# 105358-3SC001-01-A_BlockDiagram.net
KiCad netlist of a schematic drawn in Altium Designer
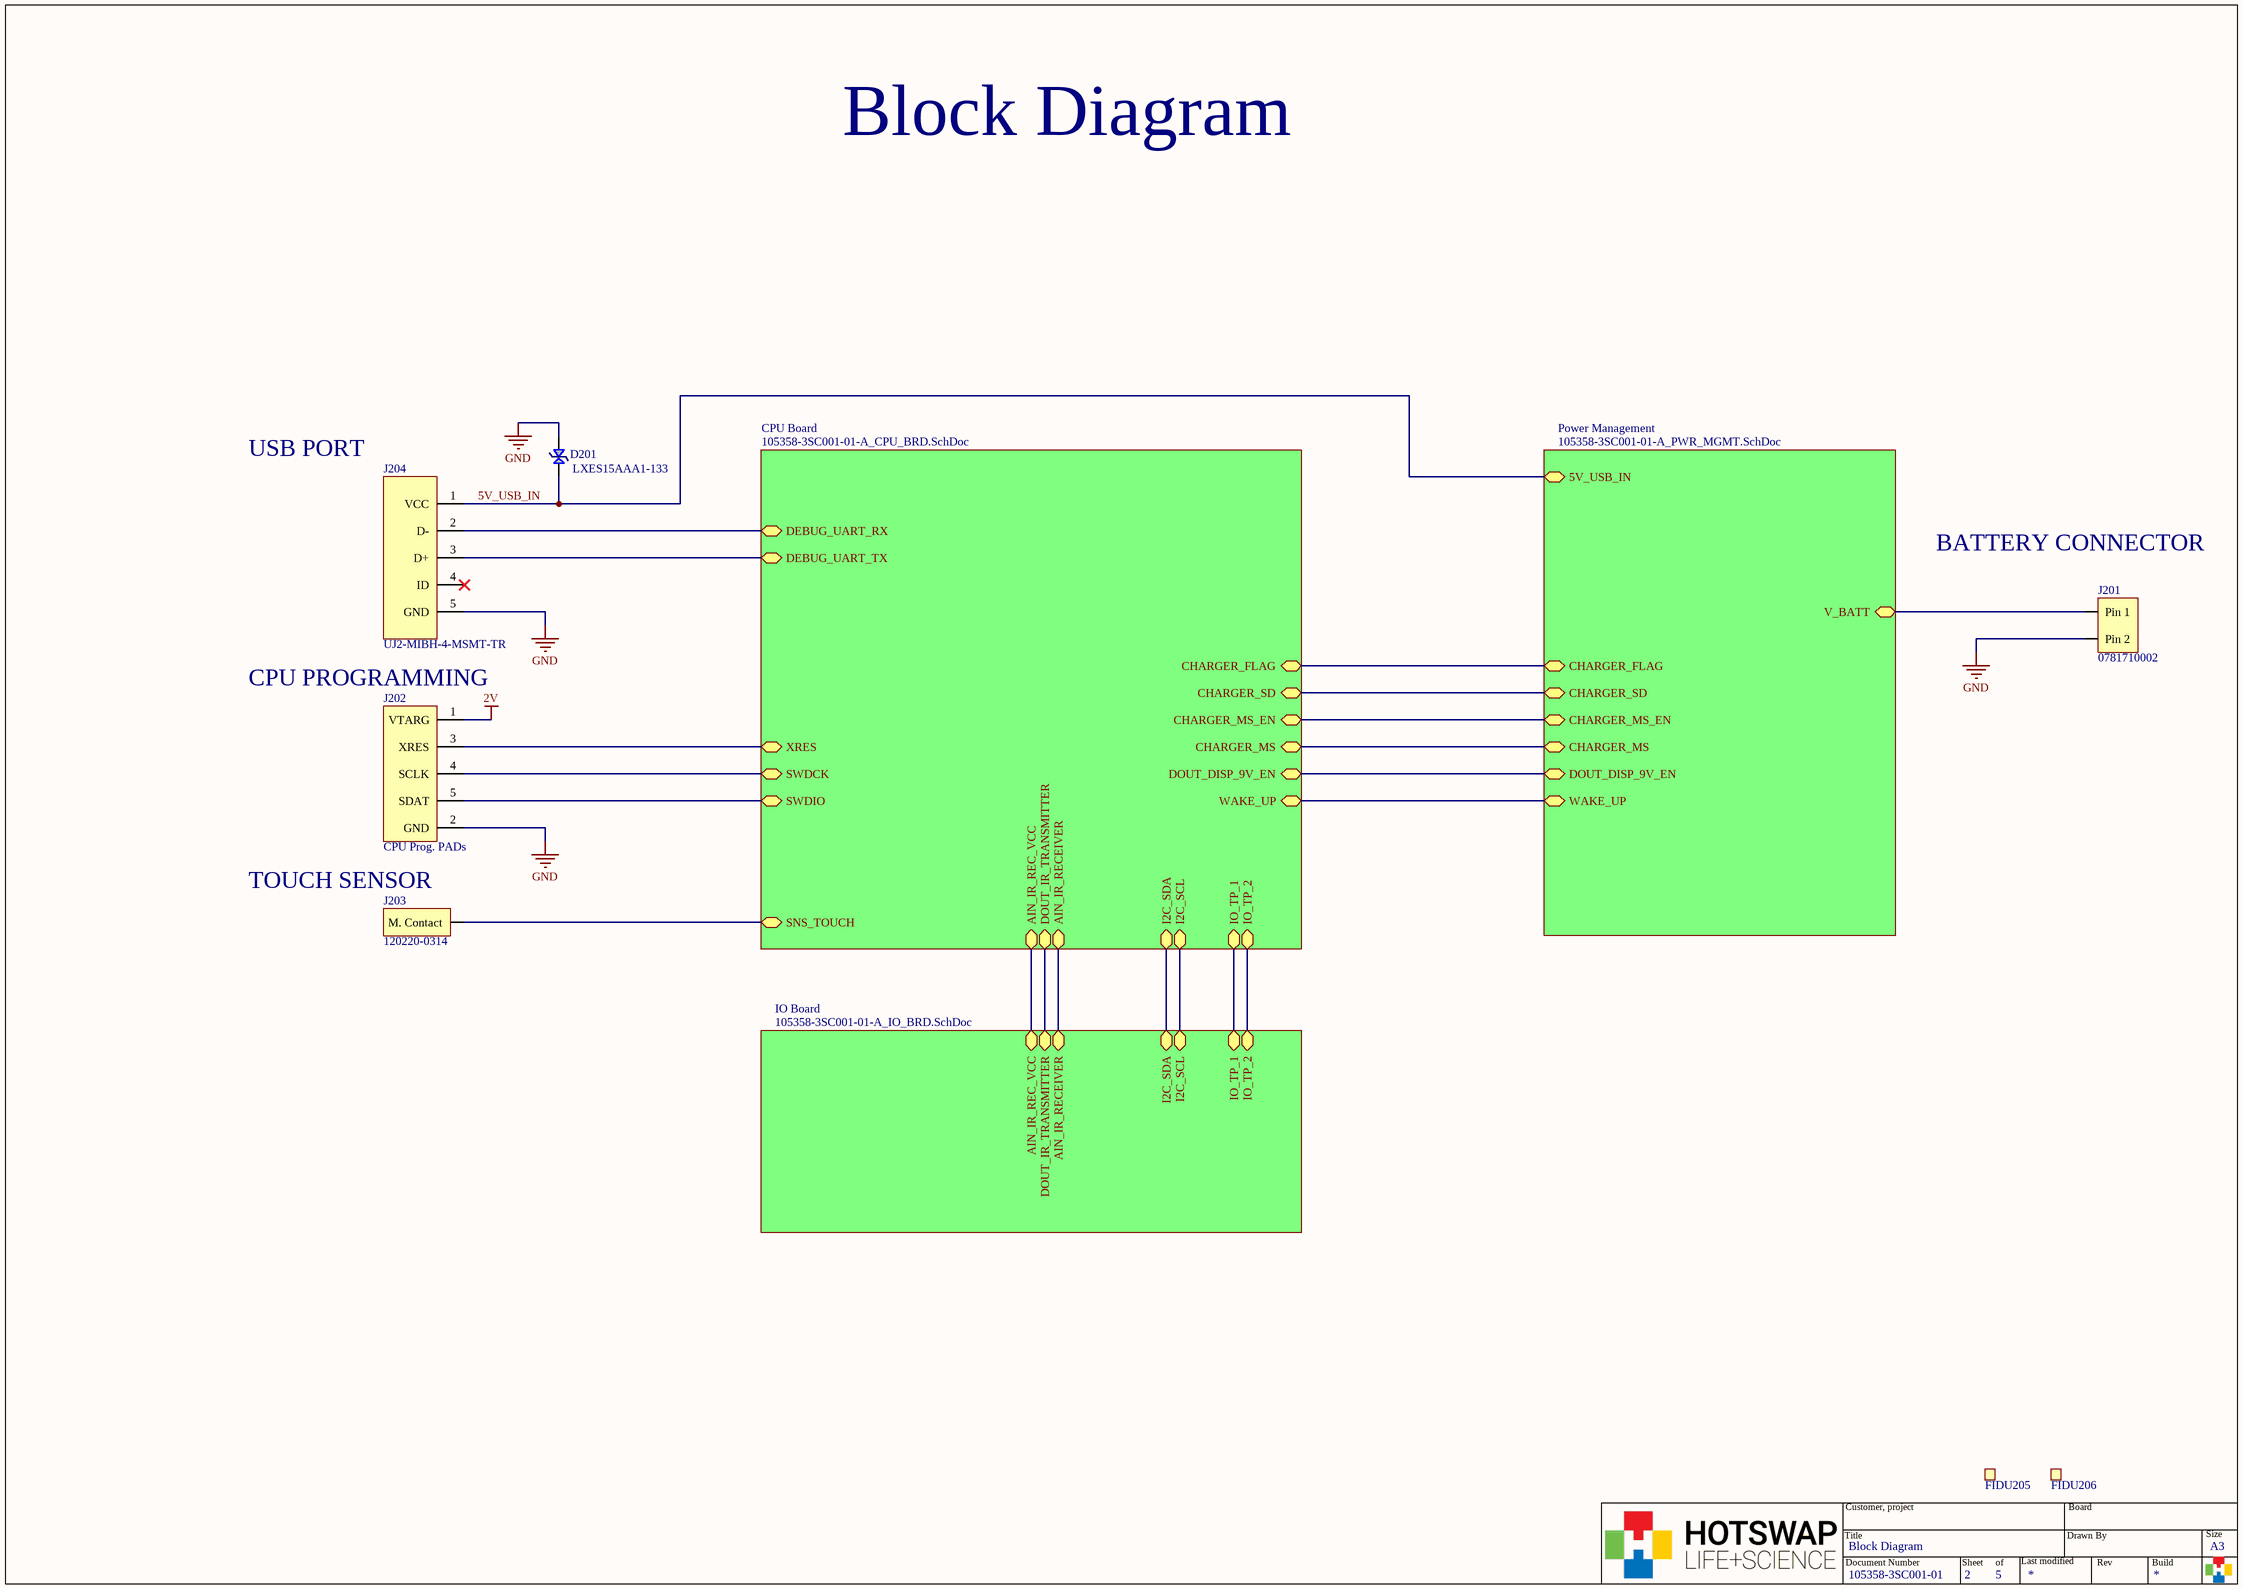
[diagram p0: 105358-3SC001-01-A_BlockDiagram.SchDoc]

(export (version "E")
  (design (tool "Eeschema 10.0.6"))
  (components
    (comp (ref "D201")
      (value "LXES15AAA1-133")
      (footprint "0402C-GENERIC")
      (description "TVS DIODE 15VWM 0402")
      (fields
        (field (name "MANUFACTURER") "Murata Electronics North America")
        (field (name "DIGI-KEY PART NUMBER") "490-13209-1-ND")
      )
      (libsource (lib "ConnectMedical") (part "TVS DIODE 15VWM 0402"))
    )
    (comp (ref "FIDU205")
      (value "FIDU-SQUARE")
      (footprint "FIDU-SQUARE")
      (description "Feducial marker Square")
      (libsource (lib "Schlib_NioxVero") (part "FIDU-SQUARE"))
    )
    (comp (ref "FIDU206")
      (value "FIDU-SQUARE")
      (footprint "FIDU-SQUARE")
      (description "Feducial marker Square")
      (libsource (lib "Schlib_NioxVero") (part "FIDU-SQUARE"))
    )
    (comp (ref "J201")
      (value "0781710002")
      (footprint "PAD 0781710002")
      (description "1.20MM WTB HEADER VERT 2POS")
      (fields (field (name "MANUFACTURER") "Molex, LLC") (field (name "DIGI-KEY PART NUMBER") "WM4459CT-ND"))
      (libsource (lib "ConnectMedical") (part "CONNECTOR 1.20MM WTB HEADER VERT 2POS"))
    )
    (comp (ref "J202")
      (value "CPU Prog. PADs")
      (footprint "PAD PROGRAMMING")
      (description "CPU Programming PADs")
      (libsource (lib "ConnectMedical") (part "PROGRAMMING PADS"))
    )
    (comp (ref "J203")
      (value "120220-0314")
      (footprint "PAD 1.0x1.95mm")
      (description "MICRO UNIVERSAL CONTACT Z 3.5MM")
      (fields
        (field (name "MANUFACTURER") "ITT Cannon, LLC")
        (field (name "DIGI-KEY PART NUMBER") "1003-2383-1-ND")
      )
      (libsource (lib "ConnectMedical") (part "MICRO UNIVERSAL CONTACT Z 3.5MM"))
    )
    (comp (ref "J204")
      (value "UJ2-MIBH-4-MSMT-TR")
      (footprint "UJ2-MIBH-4-MSMT-TR")
      (description "USB Micro B")
      (fields (field (name "MANUFACTURER") "CUI Inc.") (field (name "DIGI-KEY PART NUMBER") "102-4008-1-ND"))
      (libsource (lib "ConnectMedical") (part "UJ2-MIBH-4-MSMT-TR"))
    )
  )
  (nets
    (net (code "1") (name "/5V_USB_IN") (class "Default")
      (node (ref "D201") (pin "2") (pinfunction "2_2") (pintype "passive"))
      (node (ref "J204") (pin "1") (pinfunction "VCC_1") (pintype "passive"))
    )
    (net (code "8") (name "/DEBUG_UART_RX") (class "Default")
      (node (ref "J204") (pin "2") (pinfunction "D-_2") (pintype "passive"))
    )
    (net (code "9") (name "/DEBUG_UART_TX") (class "Default")
      (node (ref "J204") (pin "3") (pinfunction "D+_3") (pintype "passive"))
    )
    (net (code "16") (name "/SNS_TOUCH") (class "Default")
      (node (ref "J203") (pin "1") (pinfunction "M._Contact_1") (pintype "passive"))
    )
    (net (code "17") (name "/SWDCK") (class "Default")
      (node (ref "J202") (pin "4") (pinfunction "SCLK_4") (pintype "passive"))
    )
    (net (code "18") (name "/SWDIO") (class "Default")
      (node (ref "J202") (pin "5") (pinfunction "SDAT_5") (pintype "passive"))
    )
    (net (code "19") (name "/V_BATT") (class "Default")
      (node (ref "J201") (pin "1") (pinfunction "Pin_1_1") (pintype "passive"))
    )
    (net (code "21") (name "/XRES") (class "Default")
      (node (ref "J202") (pin "3") (pinfunction "XRES_3") (pintype "passive"))
    )
    (net (code "22") (name "2V") (class "Default")
      (node (ref "J202") (pin "1") (pinfunction "VTARG_1") (pintype "passive"))
    )
    (net (code "23") (name "GND") (class "Default")
      (node (ref "D201") (pin "1") (pinfunction "1_1") (pintype "passive"))
      (node (ref "J201") (pin "2") (pinfunction "Pin_2_2") (pintype "passive"))
      (node (ref "J202") (pin "2") (pinfunction "GND_2") (pintype "passive"))
      (node (ref "J204") (pin "5") (pinfunction "GND_5") (pintype "passive"))
    )
    (net (code "24") (name "unconnected-(J204-ID-Pad4)") (class "Default")
      (node (ref "J204") (pin "4") (pinfunction "ID_4") (pintype "passive+no_connect"))
    )
  )
)
